# Pro_Trinket_Keyboard_V3_4.net
KiCad netlist of a schematic drawn in EAGLE
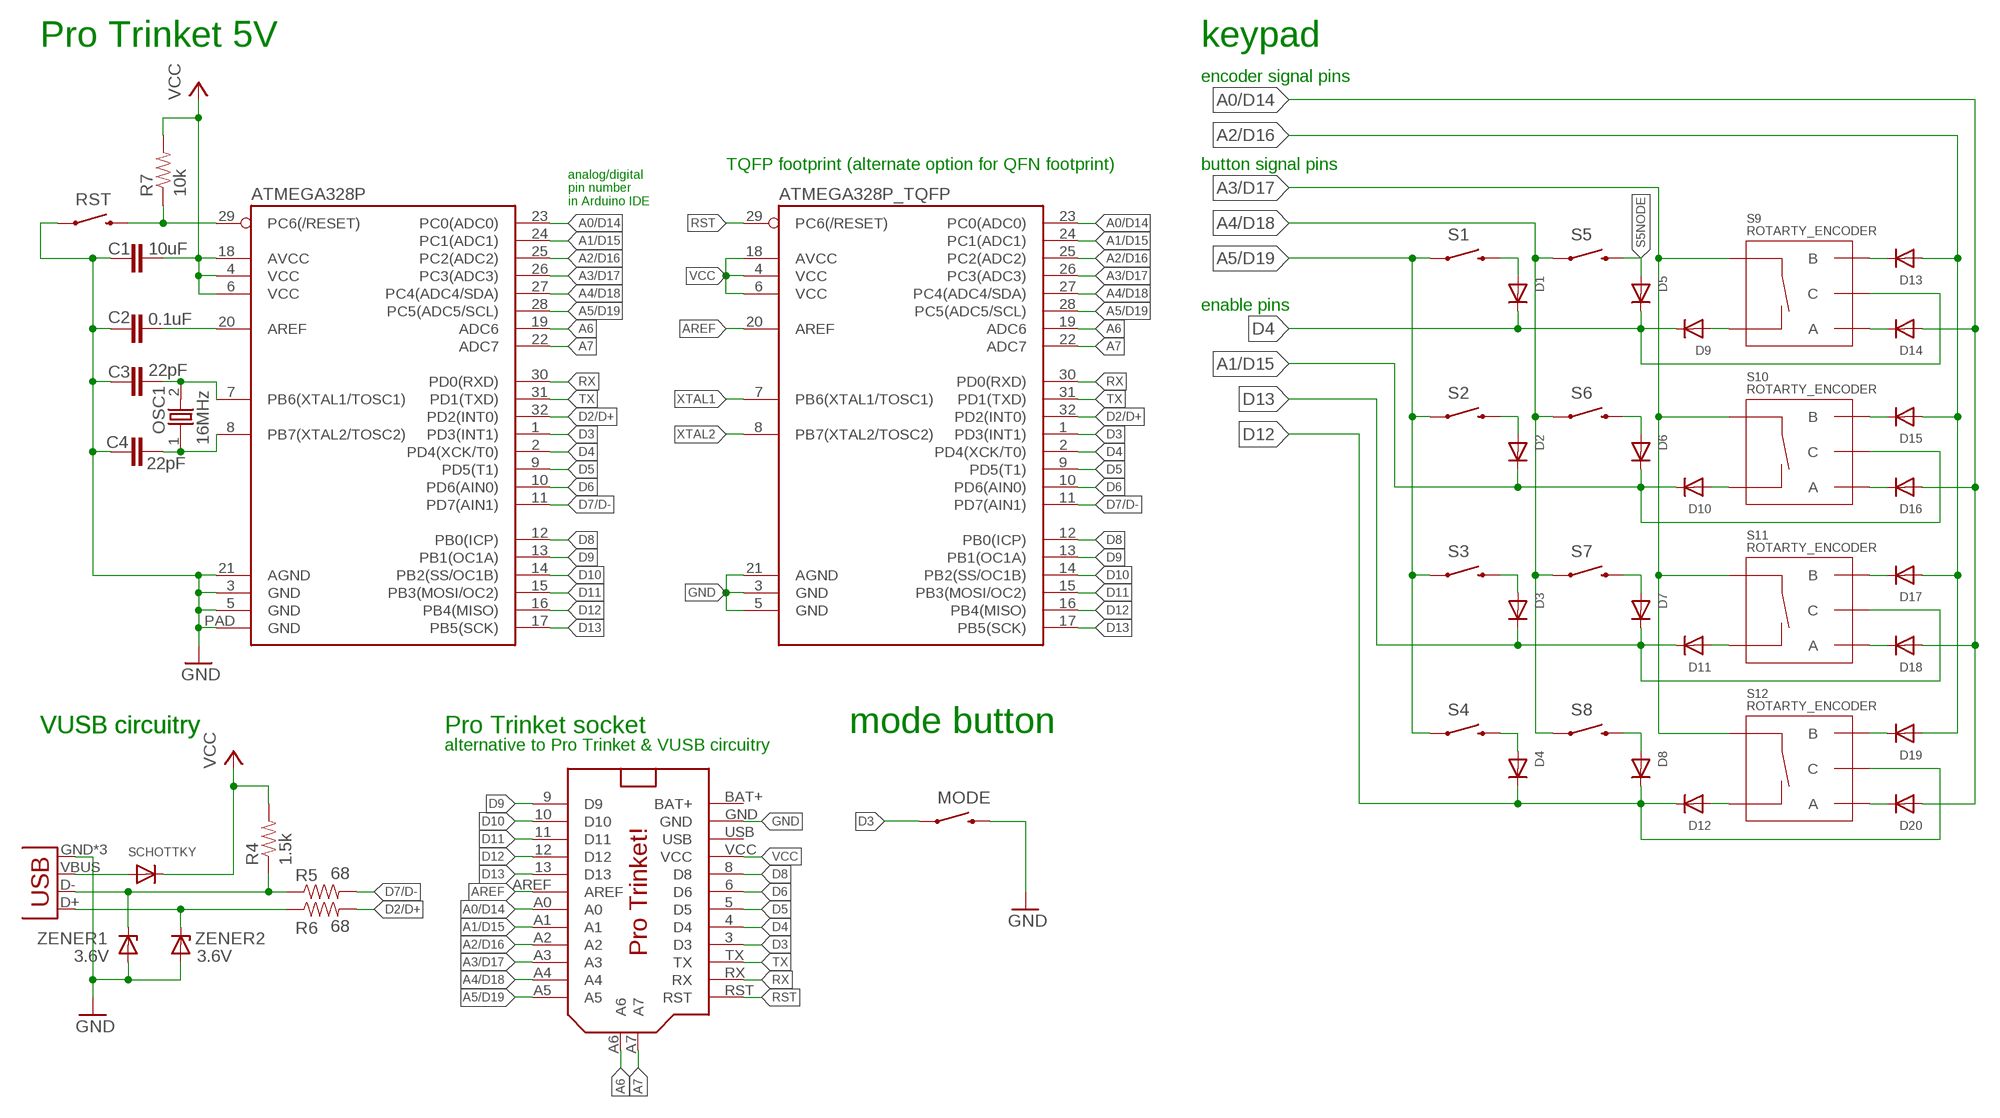
[diagram p0: schematic, sheet 1, part 1 of 2]
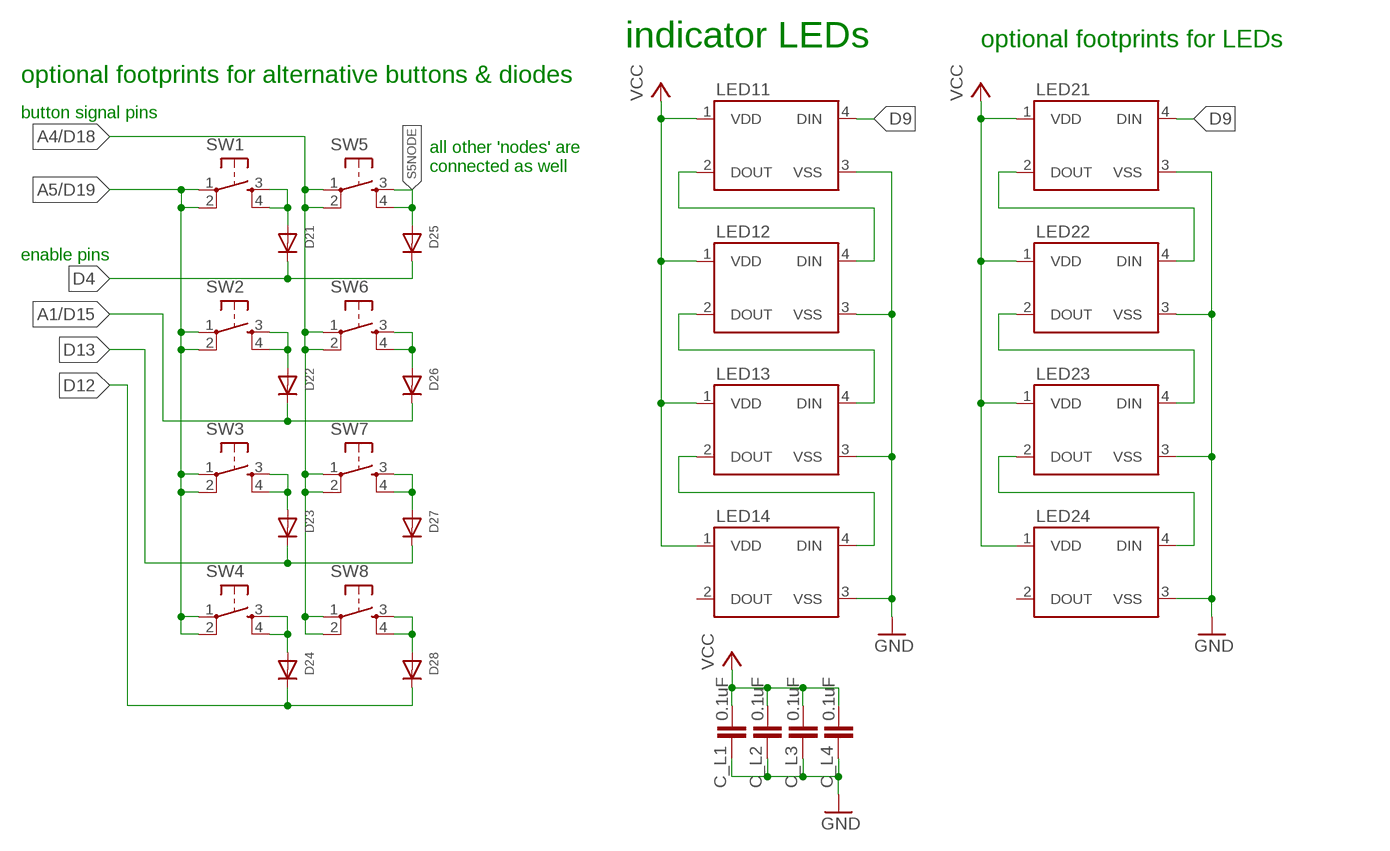
[diagram p1: schematic, sheet 1, part 2 of 2]

(export (version "E")
  (design (tool "Eeschema 10.0.6"))
  (components
    (comp (ref "ATMEGA328P")
      (value "ATMEGA328P_MLFMLF32")
      (footprint "eagle-import:MLF32-PAD")
      (libsource (lib "eagle-import") (part "ATMEGA328P_MLFMLF32"))
    )
    (comp (ref "ATMEGA328P_TQFP")
      (value "ATMEGA328P_TQFP")
      (footprint "eagle-import:TQFP32-08")
      (libsource (lib "eagle-import") (part "ATMEGA328P_TQFP"))
    )
    (comp (ref "C1")
      (value "10uF")
      (footprint "eagle-import:0603-CAP")
      (libsource (lib "eagle-import") (part "10UF-6.3V-20%(0603)"))
    )
    (comp (ref "C2")
      (value "0.1uF")
      (footprint "eagle-import:0603-CAP")
      (libsource (lib "eagle-import") (part "22PF-50V-5%(0603)"))
    )
    (comp (ref "C3")
      (value "22pF")
      (footprint "eagle-import:0603-CAP")
      (libsource (lib "eagle-import") (part "22PF-50V-5%(0603)"))
    )
    (comp (ref "C4")
      (value "22pF")
      (footprint "eagle-import:0603-CAP")
      (libsource (lib "eagle-import") (part "22PF-50V-5%(0603)"))
    )
    (comp (ref "C_L1")
      (value "0.1uF")
      (footprint "eagle-import:0603-CAP")
      (libsource (lib "eagle-import") (part "22PF-50V-5%(0603)"))
    )
    (comp (ref "C_L2")
      (value "0.1uF")
      (footprint "eagle-import:0603-CAP")
      (libsource (lib "eagle-import") (part "22PF-50V-5%(0603)"))
    )
    (comp (ref "C_L3")
      (value "0.1uF")
      (footprint "eagle-import:0603-CAP")
      (libsource (lib "eagle-import") (part "22PF-50V-5%(0603)"))
    )
    (comp (ref "C_L4")
      (value "0.1uF")
      (footprint "eagle-import:0603-CAP")
      (libsource (lib "eagle-import") (part "22PF-50V-5%(0603)"))
    )
    (comp (ref "D1")
      (value "DIODESOD-123")
      (footprint "eagle-import:SOD-123")
      (libsource (lib "eagle-import") (part "DIODESOD-123"))
    )
    (comp (ref "D2")
      (value "DIODESOD-123")
      (footprint "eagle-import:SOD-123")
      (libsource (lib "eagle-import") (part "DIODESOD-123"))
    )
    (comp (ref "D3")
      (value "DIODESOD-123")
      (footprint "eagle-import:SOD-123")
      (libsource (lib "eagle-import") (part "DIODESOD-123"))
    )
    (comp (ref "D4")
      (value "DIODESOD-123")
      (footprint "eagle-import:SOD-123")
      (libsource (lib "eagle-import") (part "DIODESOD-123"))
    )
    (comp (ref "D5")
      (value "DIODESOD-123")
      (footprint "eagle-import:SOD-123")
      (libsource (lib "eagle-import") (part "DIODESOD-123"))
    )
    (comp (ref "D6")
      (value "DIODESOD-123")
      (footprint "eagle-import:SOD-123")
      (libsource (lib "eagle-import") (part "DIODESOD-123"))
    )
    (comp (ref "D7")
      (value "DIODESOD-123")
      (footprint "eagle-import:SOD-123")
      (libsource (lib "eagle-import") (part "DIODESOD-123"))
    )
    (comp (ref "D8")
      (value "DIODESOD-123")
      (footprint "eagle-import:SOD-123")
      (libsource (lib "eagle-import") (part "DIODESOD-123"))
    )
    (comp (ref "D9")
      (value "DIODESOD-123")
      (footprint "eagle-import:SOD-123")
      (libsource (lib "eagle-import") (part "DIODESOD-123"))
    )
    (comp (ref "D10")
      (value "DIODESOD-123")
      (footprint "eagle-import:SOD-123")
      (libsource (lib "eagle-import") (part "DIODESOD-123"))
    )
    (comp (ref "D11")
      (value "DIODESOD-123")
      (footprint "eagle-import:SOD-123")
      (libsource (lib "eagle-import") (part "DIODESOD-123"))
    )
    (comp (ref "D12")
      (value "DIODESOD-123")
      (footprint "eagle-import:SOD-123")
      (libsource (lib "eagle-import") (part "DIODESOD-123"))
    )
    (comp (ref "D13")
      (value "DIODESOD-123")
      (footprint "eagle-import:SOD-123")
      (libsource (lib "eagle-import") (part "DIODESOD-123"))
    )
    (comp (ref "D14")
      (value "DIODESOD-123")
      (footprint "eagle-import:SOD-123")
      (libsource (lib "eagle-import") (part "DIODESOD-123"))
    )
    (comp (ref "D15")
      (value "DIODESOD-123")
      (footprint "eagle-import:SOD-123")
      (libsource (lib "eagle-import") (part "DIODESOD-123"))
    )
    (comp (ref "D16")
      (value "DIODESOD-123")
      (footprint "eagle-import:SOD-123")
      (libsource (lib "eagle-import") (part "DIODESOD-123"))
    )
    (comp (ref "D17")
      (value "DIODESOD-123")
      (footprint "eagle-import:SOD-123")
      (libsource (lib "eagle-import") (part "DIODESOD-123"))
    )
    (comp (ref "D18")
      (value "DIODESOD-123")
      (footprint "eagle-import:SOD-123")
      (libsource (lib "eagle-import") (part "DIODESOD-123"))
    )
    (comp (ref "D19")
      (value "DIODESOD-123")
      (footprint "eagle-import:SOD-123")
      (libsource (lib "eagle-import") (part "DIODESOD-123"))
    )
    (comp (ref "D20")
      (value "DIODESOD-123")
      (footprint "eagle-import:SOD-123")
      (libsource (lib "eagle-import") (part "DIODESOD-123"))
    )
    (comp (ref "D21")
      (value "DIODESOD-123")
      (footprint "eagle-import:SOD-123")
      (libsource (lib "eagle-import") (part "DIODESOD-123"))
    )
    (comp (ref "D22")
      (value "DIODESOD-123")
      (footprint "eagle-import:SOD-123")
      (libsource (lib "eagle-import") (part "DIODESOD-123"))
    )
    (comp (ref "D23")
      (value "DIODESOD-123")
      (footprint "eagle-import:SOD-123")
      (libsource (lib "eagle-import") (part "DIODESOD-123"))
    )
    (comp (ref "D24")
      (value "DIODESOD-123")
      (footprint "eagle-import:SOD-123")
      (libsource (lib "eagle-import") (part "DIODESOD-123"))
    )
    (comp (ref "D25")
      (value "DIODESOD-123")
      (footprint "eagle-import:SOD-123")
      (libsource (lib "eagle-import") (part "DIODESOD-123"))
    )
    (comp (ref "D26")
      (value "DIODESOD-123")
      (footprint "eagle-import:SOD-123")
      (libsource (lib "eagle-import") (part "DIODESOD-123"))
    )
    (comp (ref "D27")
      (value "DIODESOD-123")
      (footprint "eagle-import:SOD-123")
      (libsource (lib "eagle-import") (part "DIODESOD-123"))
    )
    (comp (ref "D28")
      (value "DIODESOD-123")
      (footprint "eagle-import:SOD-123")
      (libsource (lib "eagle-import") (part "DIODESOD-123"))
    )
    (comp (ref "LED11")
      (value "WS2812B")
      (footprint "eagle-import:WS2812B")
      (libsource (lib "eagle-import") (part "WS2812B"))
    )
    (comp (ref "LED12")
      (value "WS2812B")
      (footprint "eagle-import:WS2812B")
      (libsource (lib "eagle-import") (part "WS2812B"))
    )
    (comp (ref "LED13")
      (value "WS2812B")
      (footprint "eagle-import:WS2812B")
      (libsource (lib "eagle-import") (part "WS2812B"))
    )
    (comp (ref "LED14")
      (value "WS2812B")
      (footprint "eagle-import:WS2812B")
      (libsource (lib "eagle-import") (part "WS2812B"))
    )
    (comp (ref "LED21")
      (value "WS2812B")
      (footprint "eagle-import:WS2812B")
      (libsource (lib "eagle-import") (part "WS2812B"))
    )
    (comp (ref "LED22")
      (value "WS2812B")
      (footprint "eagle-import:WS2812B")
      (libsource (lib "eagle-import") (part "WS2812B"))
    )
    (comp (ref "LED23")
      (value "WS2812B")
      (footprint "eagle-import:WS2812B")
      (libsource (lib "eagle-import") (part "WS2812B"))
    )
    (comp (ref "LED24")
      (value "WS2812B")
      (footprint "eagle-import:WS2812B")
      (libsource (lib "eagle-import") (part "WS2812B"))
    )
    (comp (ref "MODE")
      (value "SWITCH-MOMENTARY-2SIDE_EZ")
      (footprint "eagle-import:TACTILE-PTH-SIDEEZ")
      (libsource (lib "eagle-import") (part "SWITCH-MOMENTARY-2SIDE_EZ"))
    )
    (comp (ref "OSC1")
      (value "16MHz")
      (footprint "eagle-import:HC-49U")
      (libsource (lib "eagle-import") (part "OSC-XTAL-HC-49U-SMD"))
    )
    (comp (ref "R4")
      (value "1.5k")
      (footprint "eagle-import:0805")
      (libsource (lib "eagle-import") (part "RESISTOR0805-RES"))
    )
    (comp (ref "R5")
      (value "68")
      (footprint "eagle-import:0805")
      (libsource (lib "eagle-import") (part "RESISTOR0805-RES"))
    )
    (comp (ref "R6")
      (value "68")
      (footprint "eagle-import:0805")
      (libsource (lib "eagle-import") (part "RESISTOR0805-RES"))
    )
    (comp (ref "R7")
      (value "10k")
      (footprint "eagle-import:0805")
      (libsource (lib "eagle-import") (part "RESISTOR0805-RES"))
    )
    (comp (ref "RST")
      (value "SWITCH-MOMENTARY-2SIDE_EZ")
      (footprint "eagle-import:TACTILE-PTH-SIDEEZ")
      (libsource (lib "eagle-import") (part "SWITCH-MOMENTARY-2SIDE_EZ"))
    )
    (comp (ref "S1")
      (value "SWITCH-MOMENTARY-212MM")
      (footprint "eagle-import:TACTILE-PTH-12MM")
      (libsource (lib "eagle-import") (part "SWITCH-MOMENTARY-212MM"))
    )
    (comp (ref "S2")
      (value "SWITCH-MOMENTARY-212MM")
      (footprint "eagle-import:TACTILE-PTH-12MM")
      (libsource (lib "eagle-import") (part "SWITCH-MOMENTARY-212MM"))
    )
    (comp (ref "S3")
      (value "SWITCH-MOMENTARY-212MM")
      (footprint "eagle-import:TACTILE-PTH-12MM")
      (libsource (lib "eagle-import") (part "SWITCH-MOMENTARY-212MM"))
    )
    (comp (ref "S4")
      (value "SWITCH-MOMENTARY-212MM")
      (footprint "eagle-import:TACTILE-PTH-12MM")
      (libsource (lib "eagle-import") (part "SWITCH-MOMENTARY-212MM"))
    )
    (comp (ref "S5")
      (value "SWITCH-MOMENTARY-212MM")
      (footprint "eagle-import:TACTILE-PTH-12MM")
      (libsource (lib "eagle-import") (part "SWITCH-MOMENTARY-212MM"))
    )
    (comp (ref "S6")
      (value "SWITCH-MOMENTARY-212MM")
      (footprint "eagle-import:TACTILE-PTH-12MM")
      (libsource (lib "eagle-import") (part "SWITCH-MOMENTARY-212MM"))
    )
    (comp (ref "S7")
      (value "SWITCH-MOMENTARY-212MM")
      (footprint "eagle-import:TACTILE-PTH-12MM")
      (libsource (lib "eagle-import") (part "SWITCH-MOMENTARY-212MM"))
    )
    (comp (ref "S8")
      (value "SWITCH-MOMENTARY-212MM")
      (footprint "eagle-import:TACTILE-PTH-12MM")
      (libsource (lib "eagle-import") (part "SWITCH-MOMENTARY-212MM"))
    )
    (comp (ref "S9")
      (value "ROTARTY_ENCODER")
      (footprint "eagle-import:ROTARY_ENC_PLAIN")
      (libsource (lib "eagle-import") (part "ROTARTY_ENCODER"))
    )
    (comp (ref "S10")
      (value "ROTARTY_ENCODER")
      (footprint "eagle-import:ROTARY_ENC_PLAIN")
      (libsource (lib "eagle-import") (part "ROTARTY_ENCODER"))
    )
    (comp (ref "S11")
      (value "ROTARTY_ENCODER")
      (footprint "eagle-import:ROTARY_ENC_PLAIN")
      (libsource (lib "eagle-import") (part "ROTARTY_ENCODER"))
    )
    (comp (ref "S12")
      (value "ROTARTY_ENCODER")
      (footprint "eagle-import:ROTARY_ENC_PLAIN")
      (libsource (lib "eagle-import") (part "ROTARTY_ENCODER"))
    )
    (comp (ref "SCHOTTKY")
      (value "DIODESMA")
      (footprint "eagle-import:SMADIODE")
      (libsource (lib "eagle-import") (part "DIODESMA"))
    )
    (comp (ref "SW1")
      (value "TACTILE-SWITCH-PTH")
      (footprint "eagle-import:TAC-SWITCH-PTH")
      (libsource (lib "eagle-import") (part "TACTILE-SWITCH-PTH"))
    )
    (comp (ref "SW2")
      (value "TACTILE-SWITCH-PTH")
      (footprint "eagle-import:TAC-SWITCH-PTH")
      (libsource (lib "eagle-import") (part "TACTILE-SWITCH-PTH"))
    )
    (comp (ref "SW3")
      (value "TACTILE-SWITCH-PTH")
      (footprint "eagle-import:TAC-SWITCH-PTH")
      (libsource (lib "eagle-import") (part "TACTILE-SWITCH-PTH"))
    )
    (comp (ref "SW4")
      (value "TACTILE-SWITCH-PTH")
      (footprint "eagle-import:TAC-SWITCH-PTH")
      (libsource (lib "eagle-import") (part "TACTILE-SWITCH-PTH"))
    )
    (comp (ref "SW5")
      (value "TACTILE-SWITCH-PTH")
      (footprint "eagle-import:TAC-SWITCH-PTH")
      (libsource (lib "eagle-import") (part "TACTILE-SWITCH-PTH"))
    )
    (comp (ref "SW6")
      (value "TACTILE-SWITCH-PTH")
      (footprint "eagle-import:TAC-SWITCH-PTH")
      (libsource (lib "eagle-import") (part "TACTILE-SWITCH-PTH"))
    )
    (comp (ref "SW7")
      (value "TACTILE-SWITCH-PTH")
      (footprint "eagle-import:TAC-SWITCH-PTH")
      (libsource (lib "eagle-import") (part "TACTILE-SWITCH-PTH"))
    )
    (comp (ref "SW8")
      (value "TACTILE-SWITCH-PTH")
      (footprint "eagle-import:TAC-SWITCH-PTH")
      (libsource (lib "eagle-import") (part "TACTILE-SWITCH-PTH"))
    )
    (comp (ref "U$2")
      (value "PRO_TRINKET")
      (footprint "eagle-import:PROTRINKET")
      (libsource (lib "eagle-import") (part "PRO_TRINKET"))
    )
    (comp (ref "UUSB")
      (value "USB-MICROB")
      (footprint "eagle-import:USB-MICROB")
      (libsource (lib "eagle-import") (part "USB-MICROB"))
    )
    (comp (ref "ZENER1")
      (value "3.6V")
      (footprint "eagle-import:SOD80C")
      (libsource (lib "eagle-import") (part "ZENER-DIODESOD80C"))
    )
    (comp (ref "ZENER2")
      (value "3.6V")
      (footprint "eagle-import:SOD80C")
      (libsource (lib "eagle-import") (part "ZENER-DIODESOD80C"))
    )
  )
  (nets
    (net (code "1") (name "/BAT+") (class "Default")
      (node (ref "U$2") (pin "BAT+") (pinfunction "BAT+_BAT+") (pintype "power_in"))
    )
    (net (code "2") (name "/L1NODE") (class "Default")
      (node (ref "LED11") (pin "2") (pinfunction "DOUT_2") (pintype "output"))
      (node (ref "LED12") (pin "4") (pinfunction "DIN_4") (pintype "input"))
      (node (ref "LED21") (pin "2") (pinfunction "DOUT_2") (pintype "output"))
      (node (ref "LED22") (pin "4") (pinfunction "DIN_4") (pintype "input"))
    )
    (net (code "3") (name "/L2NODE") (class "Default")
      (node (ref "LED12") (pin "2") (pinfunction "DOUT_2") (pintype "output"))
      (node (ref "LED13") (pin "4") (pinfunction "DIN_4") (pintype "input"))
      (node (ref "LED22") (pin "2") (pinfunction "DOUT_2") (pintype "output"))
      (node (ref "LED23") (pin "4") (pinfunction "DIN_4") (pintype "input"))
    )
    (net (code "4") (name "/L3NODE") (class "Default")
      (node (ref "LED13") (pin "2") (pinfunction "DOUT_2") (pintype "output"))
      (node (ref "LED14") (pin "4") (pinfunction "DIN_4") (pintype "input"))
      (node (ref "LED23") (pin "2") (pinfunction "DOUT_2") (pintype "output"))
      (node (ref "LED24") (pin "4") (pinfunction "DIN_4") (pintype "input"))
    )
    (net (code "5") (name "/S1NODE") (class "Default")
      (node (ref "D1") (pin "A") (pinfunction "A_A") (pintype "passive"))
      (node (ref "D21") (pin "A") (pinfunction "A_A") (pintype "passive"))
      (node (ref "S1") (pin "3") (pinfunction "2_3") (pintype "passive"))
      (node (ref "S1") (pin "4") (pinfunction "2_4") (pintype "passive"))
      (node (ref "SW1") (pin "3") (pinfunction "3_3") (pintype "passive"))
      (node (ref "SW1") (pin "4") (pinfunction "4_4") (pintype "passive"))
    )
    (net (code "6") (name "/S2NODE") (class "Default")
      (node (ref "D2") (pin "A") (pinfunction "A_A") (pintype "passive"))
      (node (ref "D22") (pin "A") (pinfunction "A_A") (pintype "passive"))
      (node (ref "S2") (pin "3") (pinfunction "2_3") (pintype "passive"))
      (node (ref "S2") (pin "4") (pinfunction "2_4") (pintype "passive"))
      (node (ref "SW2") (pin "3") (pinfunction "3_3") (pintype "passive"))
      (node (ref "SW2") (pin "4") (pinfunction "4_4") (pintype "passive"))
    )
    (net (code "7") (name "/S3NODE") (class "Default")
      (node (ref "D23") (pin "A") (pinfunction "A_A") (pintype "passive"))
      (node (ref "D3") (pin "A") (pinfunction "A_A") (pintype "passive"))
      (node (ref "S3") (pin "3") (pinfunction "2_3") (pintype "passive"))
      (node (ref "S3") (pin "4") (pinfunction "2_4") (pintype "passive"))
      (node (ref "SW3") (pin "3") (pinfunction "3_3") (pintype "passive"))
      (node (ref "SW3") (pin "4") (pinfunction "4_4") (pintype "passive"))
    )
    (net (code "8") (name "/S4NODE") (class "Default")
      (node (ref "D24") (pin "A") (pinfunction "A_A") (pintype "passive"))
      (node (ref "D4") (pin "A") (pinfunction "A_A") (pintype "passive"))
      (node (ref "S4") (pin "3") (pinfunction "2_3") (pintype "passive"))
      (node (ref "S4") (pin "4") (pinfunction "2_4") (pintype "passive"))
      (node (ref "SW4") (pin "3") (pinfunction "3_3") (pintype "passive"))
      (node (ref "SW4") (pin "4") (pinfunction "4_4") (pintype "passive"))
    )
    (net (code "9") (name "/S6NODE") (class "Default")
      (node (ref "D26") (pin "A") (pinfunction "A_A") (pintype "passive"))
      (node (ref "D6") (pin "A") (pinfunction "A_A") (pintype "passive"))
      (node (ref "S6") (pin "3") (pinfunction "2_3") (pintype "passive"))
      (node (ref "S6") (pin "4") (pinfunction "2_4") (pintype "passive"))
      (node (ref "SW6") (pin "3") (pinfunction "3_3") (pintype "passive"))
      (node (ref "SW6") (pin "4") (pinfunction "4_4") (pintype "passive"))
    )
    (net (code "10") (name "/S7NODE") (class "Default")
      (node (ref "D27") (pin "A") (pinfunction "A_A") (pintype "passive"))
      (node (ref "D7") (pin "A") (pinfunction "A_A") (pintype "passive"))
      (node (ref "S7") (pin "3") (pinfunction "2_3") (pintype "passive"))
      (node (ref "S7") (pin "4") (pinfunction "2_4") (pintype "passive"))
      (node (ref "SW7") (pin "3") (pinfunction "3_3") (pintype "passive"))
      (node (ref "SW7") (pin "4") (pinfunction "4_4") (pintype "passive"))
    )
    (net (code "11") (name "/S8NODE") (class "Default")
      (node (ref "D28") (pin "A") (pinfunction "A_A") (pintype "passive"))
      (node (ref "D8") (pin "A") (pinfunction "A_A") (pintype "passive"))
      (node (ref "S8") (pin "3") (pinfunction "2_3") (pintype "passive"))
      (node (ref "S8") (pin "4") (pinfunction "2_4") (pintype "passive"))
      (node (ref "SW8") (pin "3") (pinfunction "3_3") (pintype "passive"))
      (node (ref "SW8") (pin "4") (pinfunction "4_4") (pintype "passive"))
    )
    (net (code "12") (name "/USB") (class "Default")
      (node (ref "U$2") (pin "USB") (pinfunction "USB_USB") (pintype "power_in"))
    )
    (net (code "13") (name "A0{slash}D14") (class "Default")
      (node (ref "ATMEGA328P") (pin "23") (pinfunction "PC0(ADC0)_23") (pintype "bidirectional"))
      (node (ref "ATMEGA328P_TQFP") (pin "23") (pinfunction "PC0(ADC0)_23") (pintype "bidirectional"))
      (node (ref "D14") (pin "A") (pinfunction "A_A") (pintype "passive"))
      (node (ref "D16") (pin "A") (pinfunction "A_A") (pintype "passive"))
      (node (ref "D18") (pin "A") (pinfunction "A_A") (pintype "passive"))
      (node (ref "D20") (pin "A") (pinfunction "A_A") (pintype "passive"))
      (node (ref "U$2") (pin "A0") (pinfunction "A0_A0") (pintype "bidirectional"))
    )
    (net (code "14") (name "A1{slash}D15") (class "Default")
      (node (ref "ATMEGA328P") (pin "24") (pinfunction "PC1(ADC1)_24") (pintype "bidirectional"))
      (node (ref "ATMEGA328P_TQFP") (pin "24") (pinfunction "PC1(ADC1)_24") (pintype "bidirectional"))
      (node (ref "D10") (pin "C") (pinfunction "C_C") (pintype "passive"))
      (node (ref "D2") (pin "C") (pinfunction "C_C") (pintype "passive"))
      (node (ref "D22") (pin "C") (pinfunction "C_C") (pintype "passive"))
      (node (ref "D26") (pin "C") (pinfunction "C_C") (pintype "passive"))
      (node (ref "D6") (pin "C") (pinfunction "C_C") (pintype "passive"))
      (node (ref "S10") (pin "C") (pinfunction "C_C") (pintype "bidirectional"))
      (node (ref "U$2") (pin "A1") (pinfunction "A1_A1") (pintype "bidirectional"))
    )
    (net (code "15") (name "A2{slash}D16") (class "Default")
      (node (ref "ATMEGA328P") (pin "25") (pinfunction "PC2(ADC2)_25") (pintype "bidirectional"))
      (node (ref "ATMEGA328P_TQFP") (pin "25") (pinfunction "PC2(ADC2)_25") (pintype "bidirectional"))
      (node (ref "D13") (pin "A") (pinfunction "A_A") (pintype "passive"))
      (node (ref "D15") (pin "A") (pinfunction "A_A") (pintype "passive"))
      (node (ref "D17") (pin "A") (pinfunction "A_A") (pintype "passive"))
      (node (ref "D19") (pin "A") (pinfunction "A_A") (pintype "passive"))
      (node (ref "U$2") (pin "A2") (pinfunction "A2_A2") (pintype "bidirectional"))
    )
    (net (code "16") (name "A3{slash}D17") (class "Default")
      (node (ref "ATMEGA328P") (pin "26") (pinfunction "PC3(ADC3)_26") (pintype "bidirectional"))
      (node (ref "ATMEGA328P_TQFP") (pin "26") (pinfunction "PC3(ADC3)_26") (pintype "bidirectional"))
      (node (ref "S10") (pin "SW+") (pinfunction "SW+_SW+") (pintype "bidirectional"))
      (node (ref "S11") (pin "SW+") (pinfunction "SW+_SW+") (pintype "bidirectional"))
      (node (ref "S12") (pin "SW+") (pinfunction "SW+_SW+") (pintype "bidirectional"))
      (node (ref "S9") (pin "SW+") (pinfunction "SW+_SW+") (pintype "bidirectional"))
      (node (ref "U$2") (pin "A3") (pinfunction "A3_A3") (pintype "bidirectional"))
    )
    (net (code "17") (name "A4{slash}D18") (class "Default")
      (node (ref "ATMEGA328P") (pin "27") (pinfunction "PC4(ADC4/SDA)_27") (pintype "bidirectional"))
      (node (ref "ATMEGA328P_TQFP") (pin "27") (pinfunction "PC4(ADC4/SDA)_27") (pintype "bidirectional"))
      (node (ref "S5") (pin "1") (pinfunction "1_1") (pintype "passive"))
      (node (ref "S5") (pin "2") (pinfunction "1_2") (pintype "passive"))
      (node (ref "S6") (pin "1") (pinfunction "1_1") (pintype "passive"))
      (node (ref "S6") (pin "2") (pinfunction "1_2") (pintype "passive"))
      (node (ref "S7") (pin "1") (pinfunction "1_1") (pintype "passive"))
      (node (ref "S7") (pin "2") (pinfunction "1_2") (pintype "passive"))
      (node (ref "S8") (pin "1") (pinfunction "1_1") (pintype "passive"))
      (node (ref "S8") (pin "2") (pinfunction "1_2") (pintype "passive"))
      (node (ref "SW5") (pin "1") (pinfunction "1_1") (pintype "passive"))
      (node (ref "SW5") (pin "2") (pinfunction "2_2") (pintype "passive"))
      (node (ref "SW6") (pin "1") (pinfunction "1_1") (pintype "passive"))
      (node (ref "SW6") (pin "2") (pinfunction "2_2") (pintype "passive"))
      (node (ref "SW7") (pin "1") (pinfunction "1_1") (pintype "passive"))
      (node (ref "SW7") (pin "2") (pinfunction "2_2") (pintype "passive"))
      (node (ref "SW8") (pin "1") (pinfunction "1_1") (pintype "passive"))
      (node (ref "SW8") (pin "2") (pinfunction "2_2") (pintype "passive"))
      (node (ref "U$2") (pin "A4") (pinfunction "A4_A4") (pintype "bidirectional"))
    )
    (net (code "18") (name "A5{slash}D19") (class "Default")
      (node (ref "ATMEGA328P") (pin "28") (pinfunction "PC5(ADC5/SCL)_28") (pintype "bidirectional"))
      (node (ref "ATMEGA328P_TQFP") (pin "28") (pinfunction "PC5(ADC5/SCL)_28") (pintype "bidirectional"))
      (node (ref "S1") (pin "1") (pinfunction "1_1") (pintype "passive"))
      (node (ref "S1") (pin "2") (pinfunction "1_2") (pintype "passive"))
      (node (ref "S2") (pin "1") (pinfunction "1_1") (pintype "passive"))
      (node (ref "S2") (pin "2") (pinfunction "1_2") (pintype "passive"))
      (node (ref "S3") (pin "1") (pinfunction "1_1") (pintype "passive"))
      (node (ref "S3") (pin "2") (pinfunction "1_2") (pintype "passive"))
      (node (ref "S4") (pin "1") (pinfunction "1_1") (pintype "passive"))
      (node (ref "S4") (pin "2") (pinfunction "1_2") (pintype "passive"))
      (node (ref "SW1") (pin "1") (pinfunction "1_1") (pintype "passive"))
      (node (ref "SW1") (pin "2") (pinfunction "2_2") (pintype "passive"))
      (node (ref "SW2") (pin "1") (pinfunction "1_1") (pintype "passive"))
      (node (ref "SW2") (pin "2") (pinfunction "2_2") (pintype "passive"))
      (node (ref "SW3") (pin "1") (pinfunction "1_1") (pintype "passive"))
      (node (ref "SW3") (pin "2") (pinfunction "2_2") (pintype "passive"))
      (node (ref "SW4") (pin "1") (pinfunction "1_1") (pintype "passive"))
      (node (ref "SW4") (pin "2") (pinfunction "2_2") (pintype "passive"))
      (node (ref "U$2") (pin "A5") (pinfunction "A5_A5") (pintype "bidirectional"))
    )
    (net (code "19") (name "A6") (class "Default")
      (node (ref "ATMEGA328P") (pin "19") (pinfunction "ADC6_19") (pintype "bidirectional"))
      (node (ref "ATMEGA328P_TQFP") (pin "19") (pinfunction "ADC6_19") (pintype "bidirectional"))
      (node (ref "U$2") (pin "A6") (pinfunction "A6_A6") (pintype "passive"))
    )
    (net (code "20") (name "A7") (class "Default")
      (node (ref "ATMEGA328P") (pin "22") (pinfunction "ADC7_22") (pintype "bidirectional"))
      (node (ref "ATMEGA328P_TQFP") (pin "22") (pinfunction "ADC7_22") (pintype "bidirectional"))
      (node (ref "U$2") (pin "A7") (pinfunction "A7_A7") (pintype "passive"))
    )
    (net (code "21") (name "AREF") (class "Default")
      (node (ref "ATMEGA328P") (pin "20") (pinfunction "AREF_20") (pintype "bidirectional"))
      (node (ref "ATMEGA328P_TQFP") (pin "20") (pinfunction "AREF_20") (pintype "bidirectional"))
      (node (ref "C2") (pin "2") (pinfunction "2_2") (pintype "passive"))
      (node (ref "U$2") (pin "AREF") (pinfunction "AREF_AREF") (pintype "passive"))
    )
    (net (code "22") (name "D2{slash}D+") (class "Default")
      (node (ref "ATMEGA328P") (pin "32") (pinfunction "PD2(INT0)_32") (pintype "bidirectional"))
      (node (ref "ATMEGA328P_TQFP") (pin "32") (pinfunction "PD2(INT0)_32") (pintype "bidirectional"))
      (node (ref "R6") (pin "2") (pinfunction "2_2") (pintype "passive"))
    )
    (net (code "23") (name "D3") (class "Default")
      (node (ref "ATMEGA328P") (pin "1") (pinfunction "PD3(INT1)_1") (pintype "bidirectional"))
      (node (ref "ATMEGA328P_TQFP") (pin "1") (pinfunction "PD3(INT1)_1") (pintype "bidirectional"))
      (node (ref "MODE") (pin "1") (pinfunction "1_1") (pintype "passive"))
      (node (ref "U$2") (pin "3") (pinfunction "D3_3") (pintype "bidirectional"))
    )
    (net (code "24") (name "D4") (class "Default")
      (node (ref "ATMEGA328P") (pin "2") (pinfunction "PD4(XCK/T0)_2") (pintype "bidirectional"))
      (node (ref "ATMEGA328P_TQFP") (pin "2") (pinfunction "PD4(XCK/T0)_2") (pintype "bidirectional"))
      (node (ref "D1") (pin "C") (pinfunction "C_C") (pintype "passive"))
      (node (ref "D21") (pin "C") (pinfunction "C_C") (pintype "passive"))
      (node (ref "D25") (pin "C") (pinfunction "C_C") (pintype "passive"))
      (node (ref "D5") (pin "C") (pinfunction "C_C") (pintype "passive"))
      (node (ref "D9") (pin "C") (pinfunction "C_C") (pintype "passive"))
      (node (ref "S9") (pin "C") (pinfunction "C_C") (pintype "bidirectional"))
      (node (ref "U$2") (pin "4") (pinfunction "D4_4") (pintype "bidirectional"))
    )
    (net (code "25") (name "D5") (class "Default")
      (node (ref "ATMEGA328P") (pin "9") (pinfunction "PD5(T1)_9") (pintype "bidirectional"))
      (node (ref "ATMEGA328P_TQFP") (pin "9") (pinfunction "PD5(T1)_9") (pintype "bidirectional"))
      (node (ref "U$2") (pin "5") (pinfunction "D5_5") (pintype "bidirectional"))
    )
    (net (code "26") (name "D6") (class "Default")
      (node (ref "ATMEGA328P") (pin "10") (pinfunction "PD6(AIN0)_10") (pintype "bidirectional"))
      (node (ref "ATMEGA328P_TQFP") (pin "10") (pinfunction "PD6(AIN0)_10") (pintype "bidirectional"))
      (node (ref "U$2") (pin "6") (pinfunction "D6_6") (pintype "bidirectional"))
    )
    (net (code "27") (name "D7{slash}D-") (class "Default")
      (node (ref "ATMEGA328P") (pin "11") (pinfunction "PD7(AIN1)_11") (pintype "bidirectional"))
      (node (ref "ATMEGA328P_TQFP") (pin "11") (pinfunction "PD7(AIN1)_11") (pintype "bidirectional"))
      (node (ref "R5") (pin "2") (pinfunction "2_2") (pintype "passive"))
    )
    (net (code "28") (name "D8") (class "Default")
      (node (ref "ATMEGA328P") (pin "12") (pinfunction "PB0(ICP)_12") (pintype "bidirectional"))
      (node (ref "ATMEGA328P_TQFP") (pin "12") (pinfunction "PB0(ICP)_12") (pintype "bidirectional"))
      (node (ref "U$2") (pin "8") (pinfunction "D8_8") (pintype "bidirectional"))
    )
    (net (code "29") (name "D9") (class "Default")
      (node (ref "ATMEGA328P") (pin "13") (pinfunction "PB1(OC1A)_13") (pintype "bidirectional"))
      (node (ref "ATMEGA328P_TQFP") (pin "13") (pinfunction "PB1(OC1A)_13") (pintype "bidirectional"))
      (node (ref "LED11") (pin "4") (pinfunction "DIN_4") (pintype "input"))
      (node (ref "LED21") (pin "4") (pinfunction "DIN_4") (pintype "input"))
      (node (ref "U$2") (pin "9") (pinfunction "D9_9") (pintype "bidirectional"))
    )
    (net (code "30") (name "D10") (class "Default")
      (node (ref "ATMEGA328P") (pin "14") (pinfunction "PB2(SS/OC1B)_14") (pintype "bidirectional"))
      (node (ref "ATMEGA328P_TQFP") (pin "14") (pinfunction "PB2(SS/OC1B)_14") (pintype "bidirectional"))
      (node (ref "U$2") (pin "10") (pinfunction "D10_10") (pintype "bidirectional"))
    )
    (net (code "31") (name "D11") (class "Default")
      (node (ref "ATMEGA328P") (pin "15") (pinfunction "PB3(MOSI/OC2)_15") (pintype "bidirectional"))
      (node (ref "ATMEGA328P_TQFP") (pin "15") (pinfunction "PB3(MOSI/OC2)_15") (pintype "bidirectional"))
      (node (ref "U$2") (pin "11") (pinfunction "D11_11") (pintype "bidirectional"))
    )
    (net (code "32") (name "D12") (class "Default")
      (node (ref "ATMEGA328P") (pin "16") (pinfunction "PB4(MISO)_16") (pintype "bidirectional"))
      (node (ref "ATMEGA328P_TQFP") (pin "16") (pinfunction "PB4(MISO)_16") (pintype "bidirectional"))
      (node (ref "D12") (pin "C") (pinfunction "C_C") (pintype "passive"))
      (node (ref "D24") (pin "C") (pinfunction "C_C") (pintype "passive"))
      (node (ref "D28") (pin "C") (pinfunction "C_C") (pintype "passive"))
      (node (ref "D4") (pin "C") (pinfunction "C_C") (pintype "passive"))
      (node (ref "D8") (pin "C") (pinfunction "C_C") (pintype "passive"))
      (node (ref "S12") (pin "C") (pinfunction "C_C") (pintype "bidirectional"))
      (node (ref "U$2") (pin "12") (pinfunction "D12_12") (pintype "bidirectional"))
    )
    (net (code "33") (name "D13") (class "Default")
      (node (ref "ATMEGA328P") (pin "17") (pinfunction "PB5(SCK)_17") (pintype "bidirectional"))
      (node (ref "ATMEGA328P_TQFP") (pin "17") (pinfunction "PB5(SCK)_17") (pintype "bidirectional"))
      (node (ref "D11") (pin "C") (pinfunction "C_C") (pintype "passive"))
      (node (ref "D23") (pin "C") (pinfunction "C_C") (pintype "passive"))
      (node (ref "D27") (pin "C") (pinfunction "C_C") (pintype "passive"))
      (node (ref "D3") (pin "C") (pinfunction "C_C") (pintype "passive"))
      (node (ref "D7") (pin "C") (pinfunction "C_C") (pintype "passive"))
      (node (ref "S11") (pin "C") (pinfunction "C_C") (pintype "bidirectional"))
      (node (ref "U$2") (pin "13") (pinfunction "D13_13") (pintype "bidirectional"))
    )
    (net (code "34") (name "GND") (class "Default")
      (node (ref "ATMEGA328P") (pin "21") (pinfunction "AGND_21") (pintype "bidirectional"))
      (node (ref "ATMEGA328P") (pin "3") (pinfunction "GND_3") (pintype "bidirectional"))
      (node (ref "ATMEGA328P") (pin "5") (pinfunction "GND_5") (pintype "bidirectional"))
      (node (ref "ATMEGA328P") (pin "PAD") (pinfunction "GND_PAD") (pintype "bidirectional"))
      (node (ref "ATMEGA328P_TQFP") (pin "21") (pinfunction "AGND_21") (pintype "bidirectional"))
      (node (ref "ATMEGA328P_TQFP") (pin "3") (pinfunction "GND_3") (pintype "bidirectional"))
      (node (ref "ATMEGA328P_TQFP") (pin "5") (pinfunction "GND_5") (pintype "bidirectional"))
      (node (ref "C1") (pin "1") (pinfunction "1_1") (pintype "passive"))
      (node (ref "C2") (pin "1") (pinfunction "1_1") (pintype "passive"))
      (node (ref "C3") (pin "1") (pinfunction "1_1") (pintype "passive"))
      (node (ref "C4") (pin "2") (pinfunction "2_2") (pintype "passive"))
      (node (ref "C_L1") (pin "1") (pinfunction "1_1") (pintype "passive"))
      (node (ref "C_L2") (pin "1") (pinfunction "1_1") (pintype "passive"))
      (node (ref "C_L3") (pin "1") (pinfunction "1_1") (pintype "passive"))
      (node (ref "C_L4") (pin "1") (pinfunction "1_1") (pintype "passive"))
      (node (ref "LED11") (pin "3") (pinfunction "VSS_3") (pintype "power_in"))
      (node (ref "LED12") (pin "3") (pinfunction "VSS_3") (pintype "power_in"))
      (node (ref "LED13") (pin "3") (pinfunction "VSS_3") (pintype "power_in"))
      (node (ref "LED14") (pin "3") (pinfunction "VSS_3") (pintype "power_in"))
      (node (ref "LED21") (pin "3") (pinfunction "VSS_3") (pintype "power_in"))
      (node (ref "LED22") (pin "3") (pinfunction "VSS_3") (pintype "power_in"))
      (node (ref "LED23") (pin "3") (pinfunction "VSS_3") (pintype "power_in"))
      (node (ref "LED24") (pin "3") (pinfunction "VSS_3") (pintype "power_in"))
      (node (ref "MODE") (pin "2") (pinfunction "2_2") (pintype "passive"))
      (node (ref "RST") (pin "1") (pinfunction "1_1") (pintype "passive"))
      (node (ref "U$2") (pin "GND") (pinfunction "GND_GND") (pintype "power_in"))
      (node (ref "UUSB") (pin "GND") (pinfunction "GND_GND") (pintype "bidirectional"))
      (node (ref "UUSB") (pin "MT1") (pinfunction "GND_MT1") (pintype "bidirectional"))
      (node (ref "UUSB") (pin "MT2") (pinfunction "GND_MT2") (pintype "bidirectional"))
      (node (ref "ZENER1") (pin "A") (pinfunction "A_A") (pintype "passive"))
      (node (ref "ZENER2") (pin "A") (pinfunction "A_A") (pintype "passive"))
    )
    (net (code "35") (name "Net-(D9-PadA)") (class "Default")
      (node (ref "D9") (pin "A") (pinfunction "A_A") (pintype "passive"))
      (node (ref "S9") (pin "SW-") (pinfunction "SW-_SW-") (pintype "bidirectional"))
    )
    (net (code "36") (name "Net-(D10-PadA)") (class "Default")
      (node (ref "D10") (pin "A") (pinfunction "A_A") (pintype "passive"))
      (node (ref "S10") (pin "SW-") (pinfunction "SW-_SW-") (pintype "bidirectional"))
    )
    (net (code "37") (name "Net-(D11-PadA)") (class "Default")
      (node (ref "D11") (pin "A") (pinfunction "A_A") (pintype "passive"))
      (node (ref "S11") (pin "SW-") (pinfunction "SW-_SW-") (pintype "bidirectional"))
    )
    (net (code "38") (name "Net-(D12-PadA)") (class "Default")
      (node (ref "D12") (pin "A") (pinfunction "A_A") (pintype "passive"))
      (node (ref "S12") (pin "SW-") (pinfunction "SW-_SW-") (pintype "bidirectional"))
    )
    (net (code "39") (name "Net-(D13-PadC)") (class "Default")
      (node (ref "D13") (pin "C") (pinfunction "C_C") (pintype "passive"))
      (node (ref "S9") (pin "B") (pinfunction "B_B") (pintype "bidirectional"))
    )
    (net (code "40") (name "Net-(D14-PadC)") (class "Default")
      (node (ref "D14") (pin "C") (pinfunction "C_C") (pintype "passive"))
      (node (ref "S9") (pin "A") (pinfunction "A_A") (pintype "bidirectional"))
    )
    (net (code "41") (name "Net-(D15-PadC)") (class "Default")
      (node (ref "D15") (pin "C") (pinfunction "C_C") (pintype "passive"))
      (node (ref "S10") (pin "B") (pinfunction "B_B") (pintype "bidirectional"))
    )
    (net (code "42") (name "Net-(D16-PadC)") (class "Default")
      (node (ref "D16") (pin "C") (pinfunction "C_C") (pintype "passive"))
      (node (ref "S10") (pin "A") (pinfunction "A_A") (pintype "bidirectional"))
    )
    (net (code "43") (name "Net-(D17-PadC)") (class "Default")
      (node (ref "D17") (pin "C") (pinfunction "C_C") (pintype "passive"))
      (node (ref "S11") (pin "B") (pinfunction "B_B") (pintype "bidirectional"))
    )
    (net (code "44") (name "Net-(D18-PadC)") (class "Default")
      (node (ref "D18") (pin "C") (pinfunction "C_C") (pintype "passive"))
      (node (ref "S11") (pin "A") (pinfunction "A_A") (pintype "bidirectional"))
    )
    (net (code "45") (name "Net-(D19-PadC)") (class "Default")
      (node (ref "D19") (pin "C") (pinfunction "C_C") (pintype "passive"))
      (node (ref "S12") (pin "B") (pinfunction "B_B") (pintype "bidirectional"))
    )
    (net (code "46") (name "Net-(D20-PadC)") (class "Default")
      (node (ref "D20") (pin "C") (pinfunction "C_C") (pintype "passive"))
      (node (ref "S12") (pin "A") (pinfunction "A_A") (pintype "bidirectional"))
    )
    (net (code "47") (name "Net-(R4-Pad1)") (class "Default")
      (node (ref "R4") (pin "1") (pinfunction "1_1") (pintype "passive"))
      (node (ref "R5") (pin "1") (pinfunction "1_1") (pintype "passive"))
      (node (ref "UUSB") (pin "D-") (pinfunction "D-_D-") (pintype "bidirectional"))
      (node (ref "ZENER1") (pin "C") (pinfunction "C_C") (pintype "passive"))
    )
    (net (code "48") (name "Net-(R6-Pad1)") (class "Default")
      (node (ref "R6") (pin "1") (pinfunction "1_1") (pintype "passive"))
      (node (ref "UUSB") (pin "D+") (pinfunction "D+_D+") (pintype "bidirectional"))
      (node (ref "ZENER2") (pin "C") (pinfunction "C_C") (pintype "passive"))
    )
    (net (code "49") (name "Net-(SCHOTTKY-PadA)") (class "Default")
      (node (ref "SCHOTTKY") (pin "A") (pinfunction "A_A") (pintype "passive"))
      (node (ref "UUSB") (pin "VBUS") (pinfunction "VBUS_VBUS") (pintype "bidirectional"))
    )
    (net (code "50") (name "RST") (class "Default")
      (node (ref "ATMEGA328P") (pin "29") (pinfunction "PC6(/RESET)_29") (pintype "bidirectional"))
      (node (ref "ATMEGA328P_TQFP") (pin "29") (pinfunction "PC6(/RESET)_29") (pintype "bidirectional"))
      (node (ref "R7") (pin "1") (pinfunction "1_1") (pintype "passive"))
      (node (ref "RST") (pin "2") (pinfunction "2_2") (pintype "passive"))
      (node (ref "U$2") (pin "RST") (pinfunction "RST_RST") (pintype "passive"))
    )
    (net (code "51") (name "RX") (class "Default")
      (node (ref "ATMEGA328P") (pin "30") (pinfunction "PD0(RXD)_30") (pintype "bidirectional"))
      (node (ref "ATMEGA328P_TQFP") (pin "30") (pinfunction "PD0(RXD)_30") (pintype "bidirectional"))
      (node (ref "U$2") (pin "RX") (pinfunction "RX_RX") (pintype "bidirectional"))
    )
    (net (code "52") (name "S5NODE") (class "Default")
      (node (ref "D25") (pin "A") (pinfunction "A_A") (pintype "passive"))
      (node (ref "D5") (pin "A") (pinfunction "A_A") (pintype "passive"))
      (node (ref "S5") (pin "3") (pinfunction "2_3") (pintype "passive"))
      (node (ref "S5") (pin "4") (pinfunction "2_4") (pintype "passive"))
      (node (ref "SW5") (pin "3") (pinfunction "3_3") (pintype "passive"))
      (node (ref "SW5") (pin "4") (pinfunction "4_4") (pintype "passive"))
    )
    (net (code "53") (name "TX") (class "Default")
      (node (ref "ATMEGA328P") (pin "31") (pinfunction "PD1(TXD)_31") (pintype "bidirectional"))
      (node (ref "ATMEGA328P_TQFP") (pin "31") (pinfunction "PD1(TXD)_31") (pintype "bidirectional"))
      (node (ref "U$2") (pin "TX") (pinfunction "TX_TX") (pintype "bidirectional"))
    )
    (net (code "54") (name "VCC") (class "Default")
      (node (ref "ATMEGA328P") (pin "18") (pinfunction "AVCC_18") (pintype "bidirectional"))
      (node (ref "ATMEGA328P") (pin "4") (pinfunction "VCC_4") (pintype "bidirectional"))
      (node (ref "ATMEGA328P") (pin "6") (pinfunction "VCC_6") (pintype "bidirectional"))
      (node (ref "ATMEGA328P_TQFP") (pin "18") (pinfunction "AVCC_18") (pintype "bidirectional"))
      (node (ref "ATMEGA328P_TQFP") (pin "4") (pinfunction "VCC_4") (pintype "bidirectional"))
      (node (ref "ATMEGA328P_TQFP") (pin "6") (pinfunction "VCC_6") (pintype "bidirectional"))
      (node (ref "C1") (pin "2") (pinfunction "2_2") (pintype "passive"))
      (node (ref "C_L1") (pin "2") (pinfunction "2_2") (pintype "passive"))
      (node (ref "C_L2") (pin "2") (pinfunction "2_2") (pintype "passive"))
      (node (ref "C_L3") (pin "2") (pinfunction "2_2") (pintype "passive"))
      (node (ref "C_L4") (pin "2") (pinfunction "2_2") (pintype "passive"))
      (node (ref "LED11") (pin "1") (pinfunction "VDD_1") (pintype "power_in"))
      (node (ref "LED12") (pin "1") (pinfunction "VDD_1") (pintype "power_in"))
      (node (ref "LED13") (pin "1") (pinfunction "VDD_1") (pintype "power_in"))
      (node (ref "LED14") (pin "1") (pinfunction "VDD_1") (pintype "power_in"))
      (node (ref "LED21") (pin "1") (pinfunction "VDD_1") (pintype "power_in"))
      (node (ref "LED22") (pin "1") (pinfunction "VDD_1") (pintype "power_in"))
      (node (ref "LED23") (pin "1") (pinfunction "VDD_1") (pintype "power_in"))
      (node (ref "LED24") (pin "1") (pinfunction "VDD_1") (pintype "power_in"))
      (node (ref "R4") (pin "2") (pinfunction "2_2") (pintype "passive"))
      (node (ref "R7") (pin "2") (pinfunction "2_2") (pintype "passive"))
      (node (ref "SCHOTTKY") (pin "C") (pinfunction "C_C") (pintype "passive"))
      (node (ref "U$2") (pin "VCC") (pinfunction "VCC_VCC") (pintype "power_in"))
    )
    (net (code "55") (name "XTAL1") (class "Default")
      (node (ref "ATMEGA328P") (pin "7") (pinfunction "PB6(XTAL1/TOSC1)_7") (pintype "bidirectional"))
      (node (ref "ATMEGA328P_TQFP") (pin "7") (pinfunction "PB6(XTAL1/TOSC1)_7") (pintype "bidirectional"))
      (node (ref "C3") (pin "2") (pinfunction "2_2") (pintype "passive"))
      (node (ref "OSC1") (pin "2") (pinfunction "2_2") (pintype "passive"))
    )
    (net (code "56") (name "XTAL2") (class "Default")
      (node (ref "ATMEGA328P") (pin "8") (pinfunction "PB7(XTAL2/TOSC2)_8") (pintype "bidirectional"))
      (node (ref "ATMEGA328P_TQFP") (pin "8") (pinfunction "PB7(XTAL2/TOSC2)_8") (pintype "bidirectional"))
      (node (ref "C4") (pin "1") (pinfunction "1_1") (pintype "passive"))
      (node (ref "OSC1") (pin "1") (pinfunction "1_1") (pintype "passive"))
    )
    (net (code "57") (name "unconnected-(LED14-DOUT-Pad2)") (class "Default")
      (node (ref "LED14") (pin "2") (pinfunction "DOUT_2") (pintype "output"))
    )
    (net (code "58") (name "unconnected-(LED24-DOUT-Pad2)") (class "Default")
      (node (ref "LED24") (pin "2") (pinfunction "DOUT_2") (pintype "output"))
    )
  )
)
